# breakout.net
KiCad netlist of a schematic drawn in EAGLE
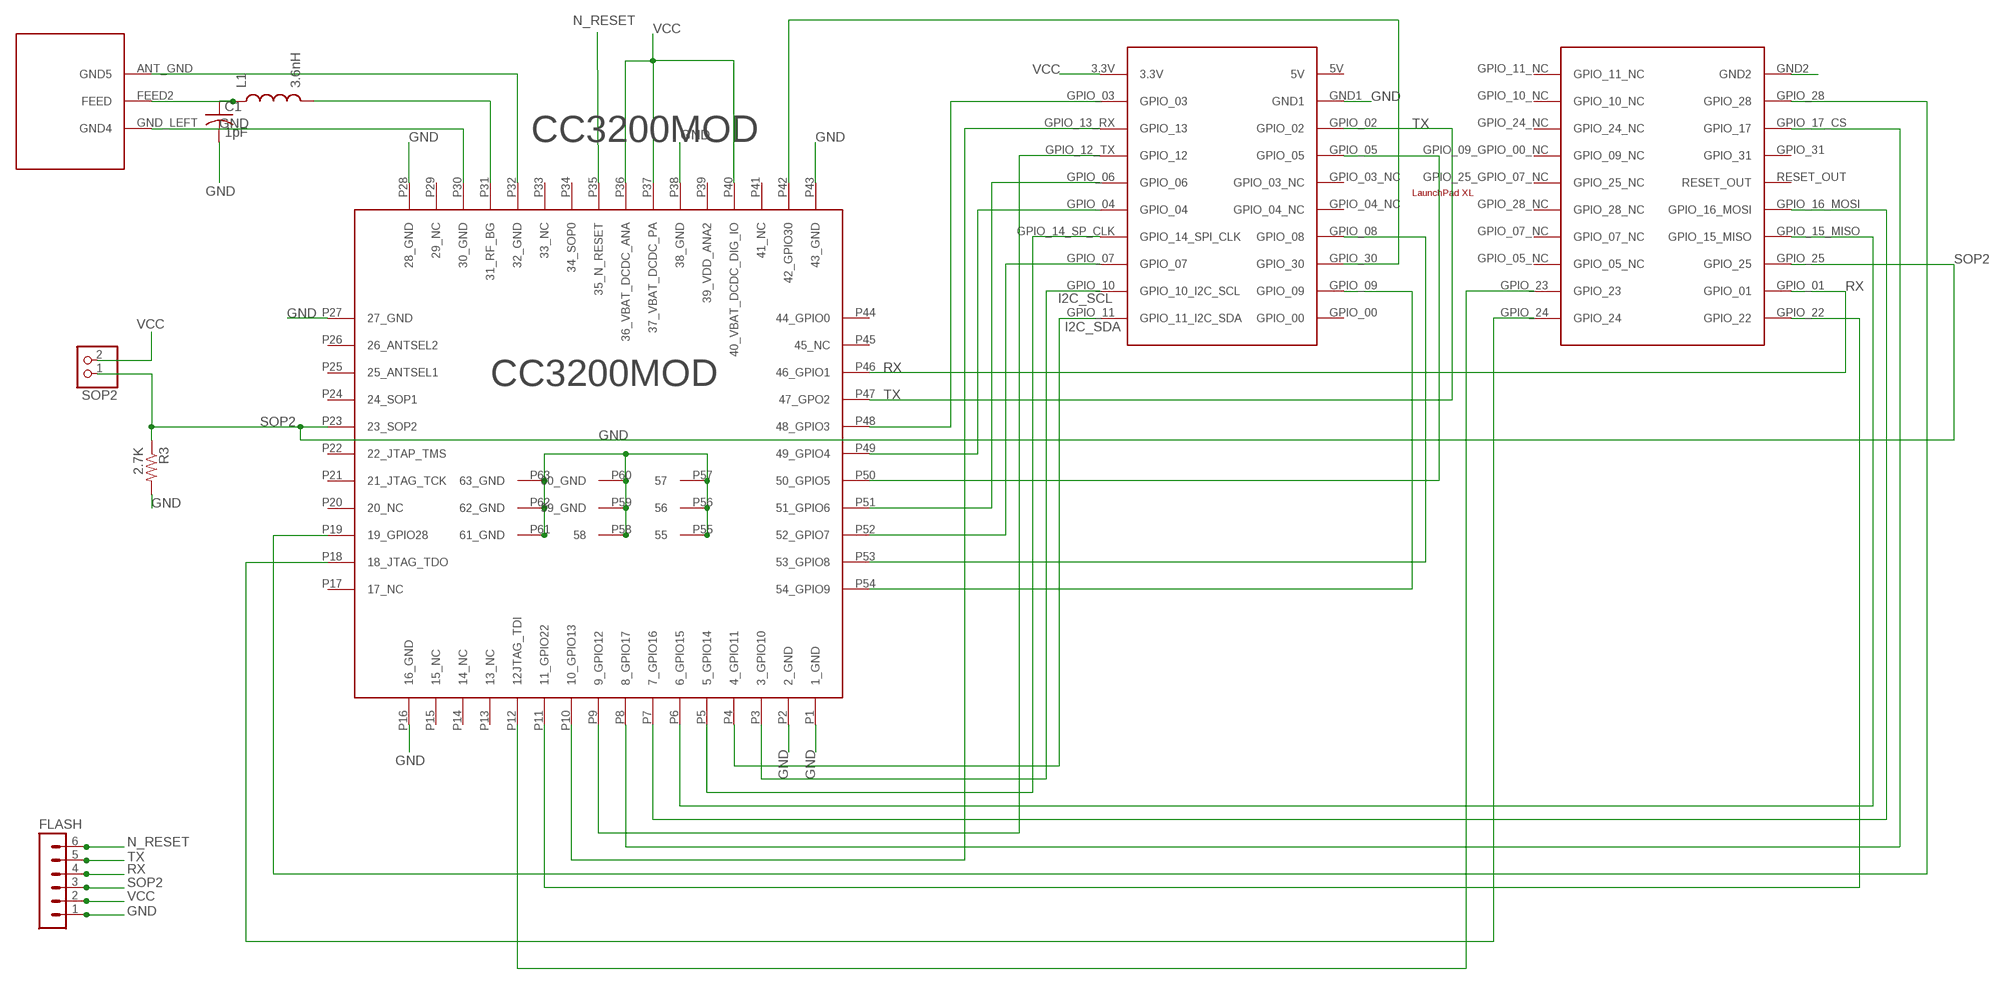
[diagram p0: schematic, sheet 1]
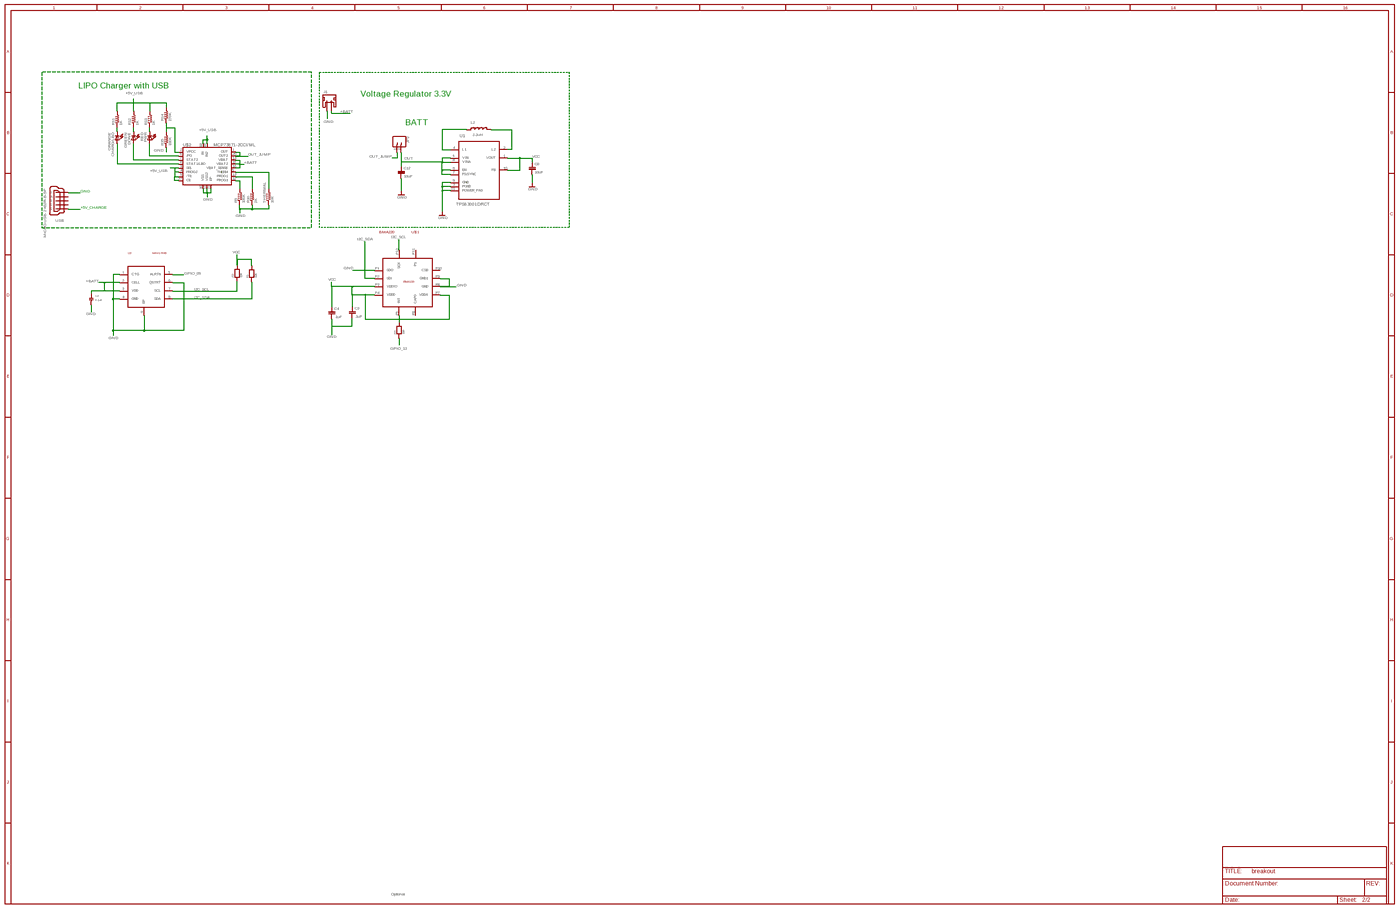
[diagram p1: schematic, sheet 2, overview]
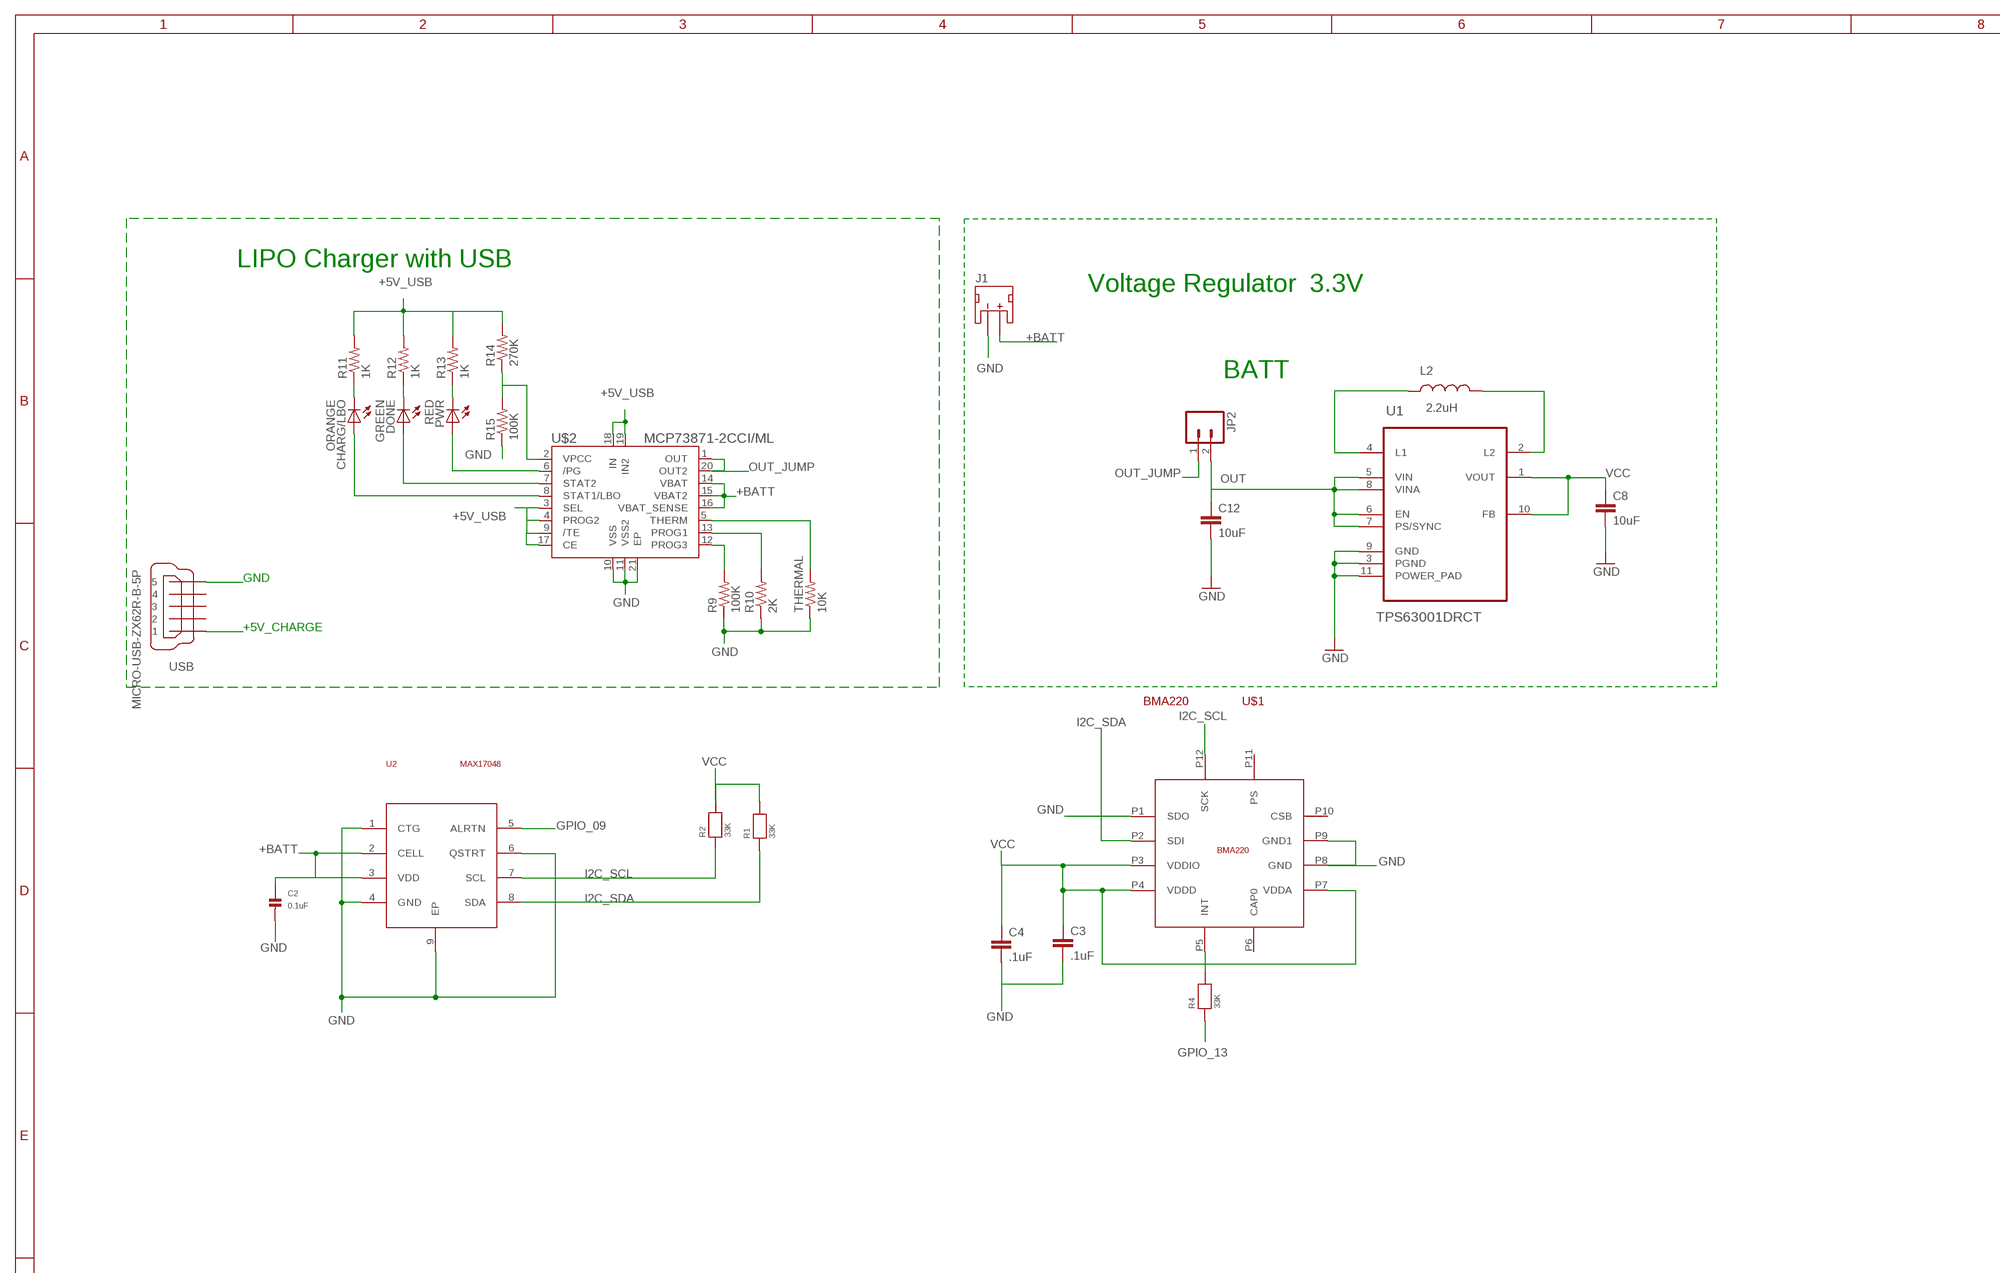
[diagram p2: schematic, sheet 2, part 1 of 4]
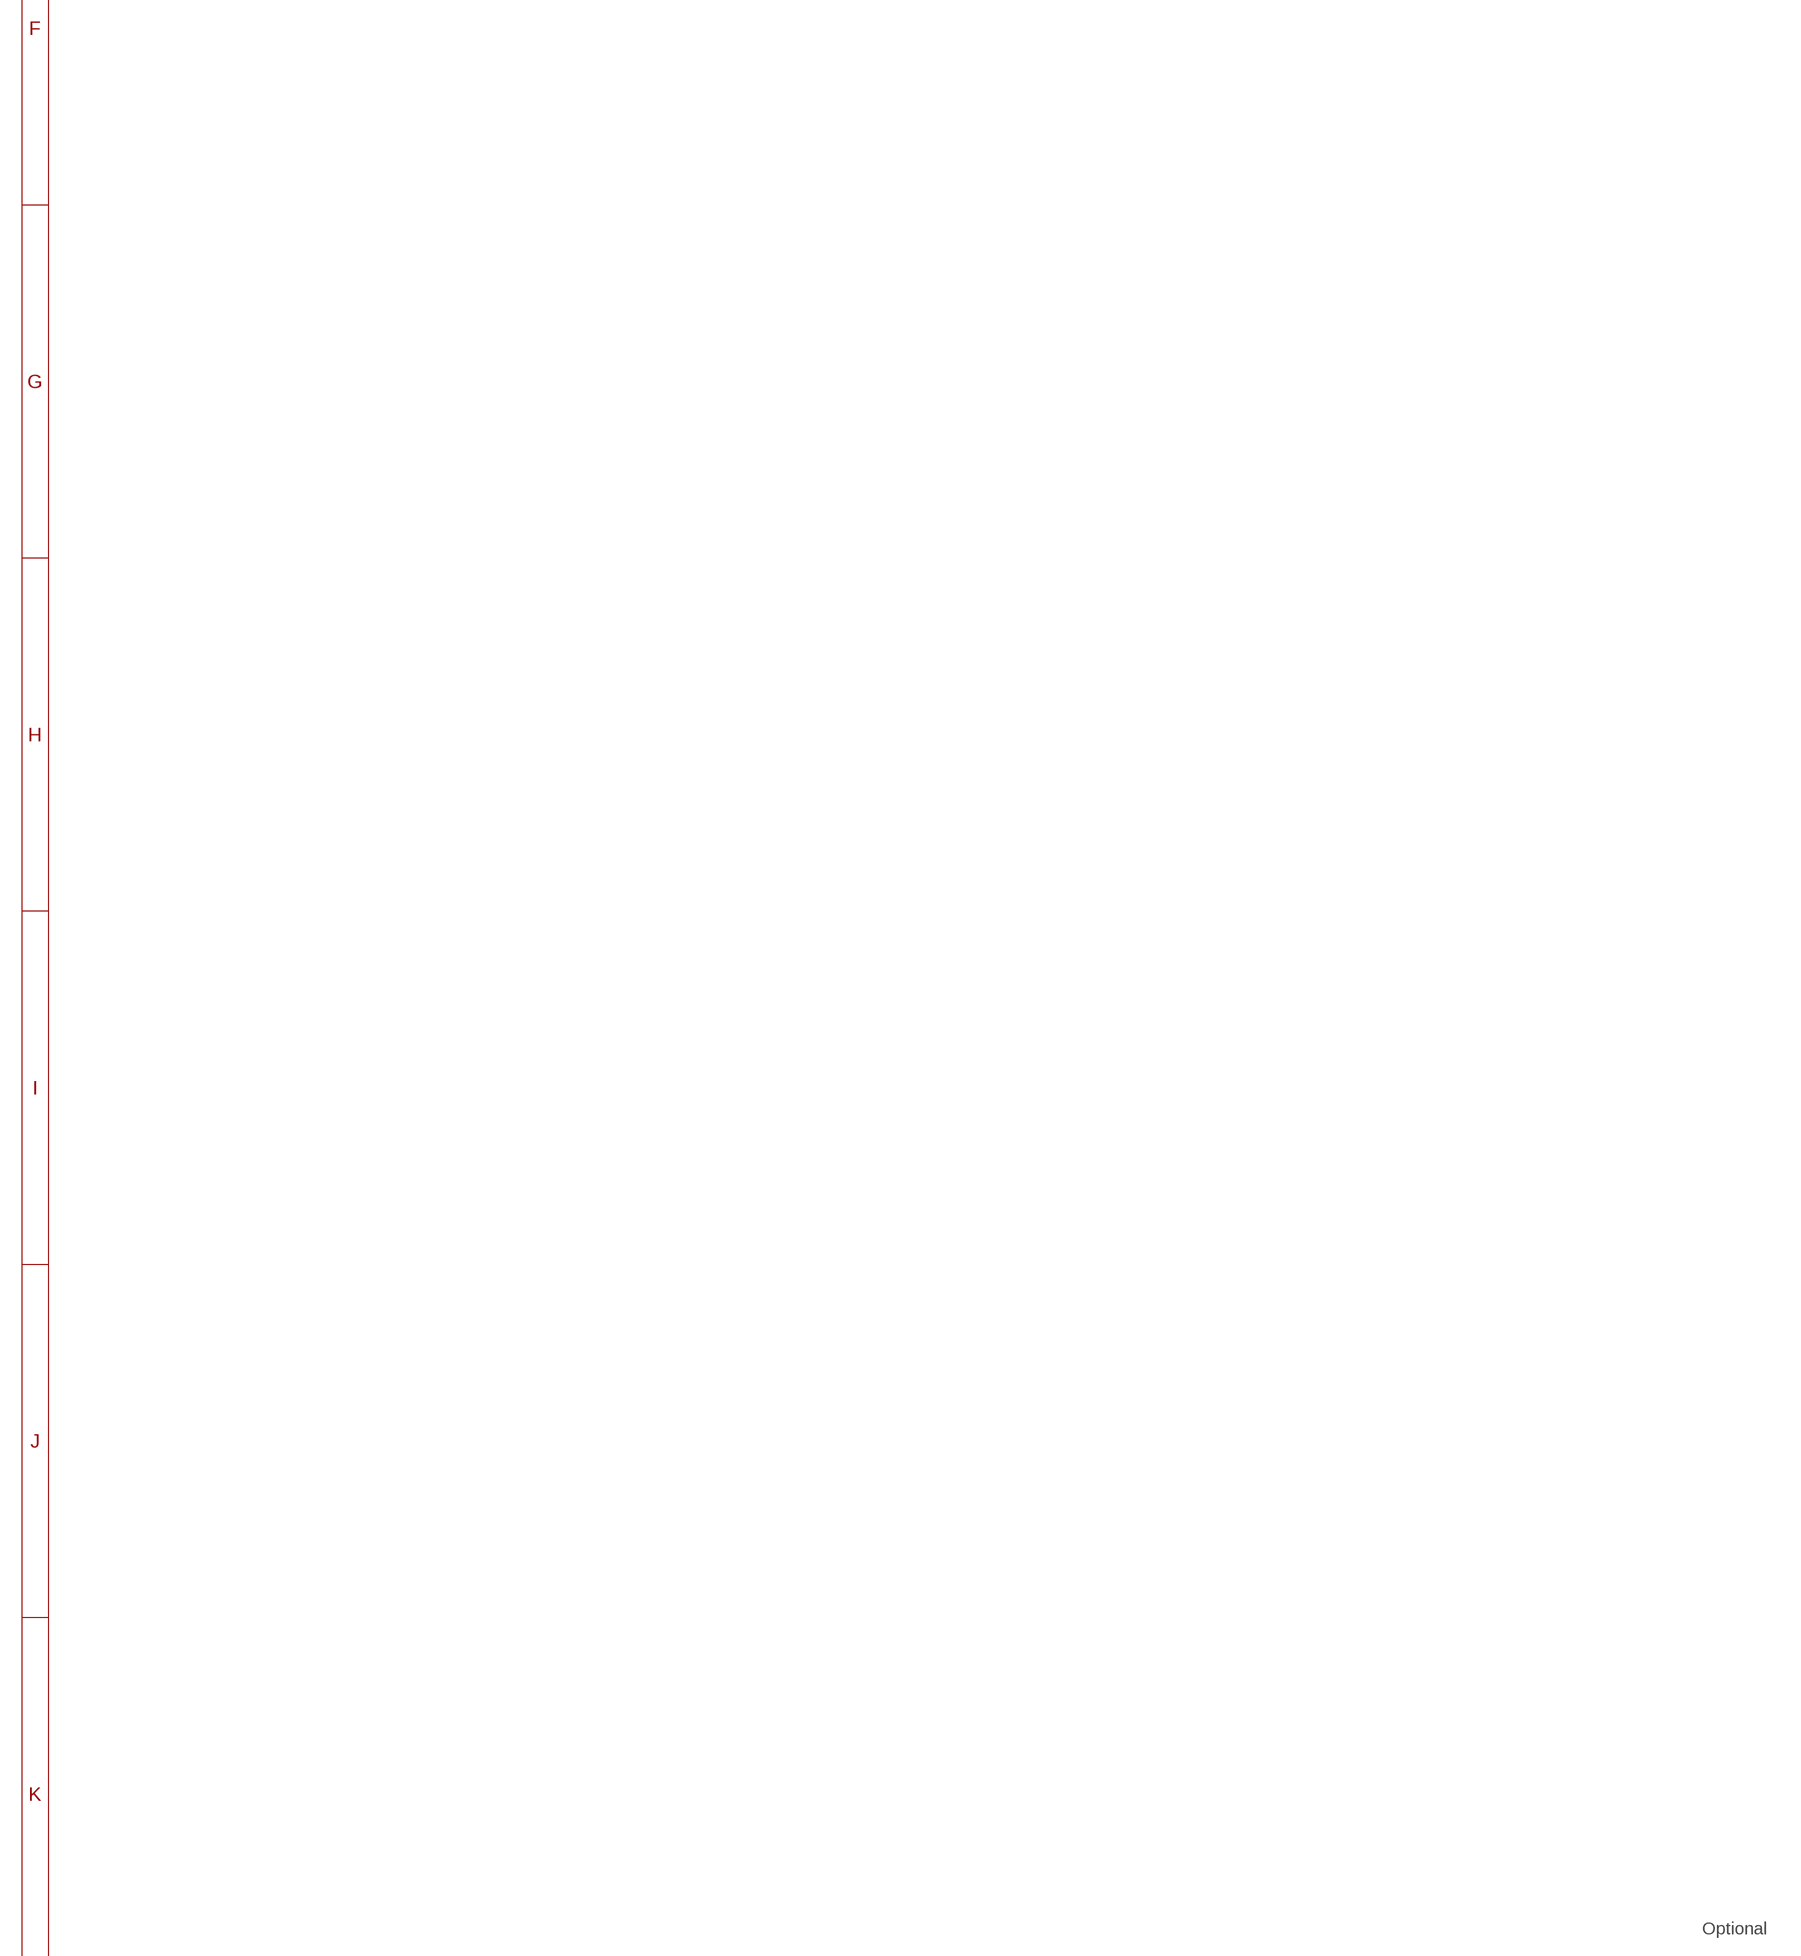
[diagram p3: schematic, sheet 2, part 2 of 4]
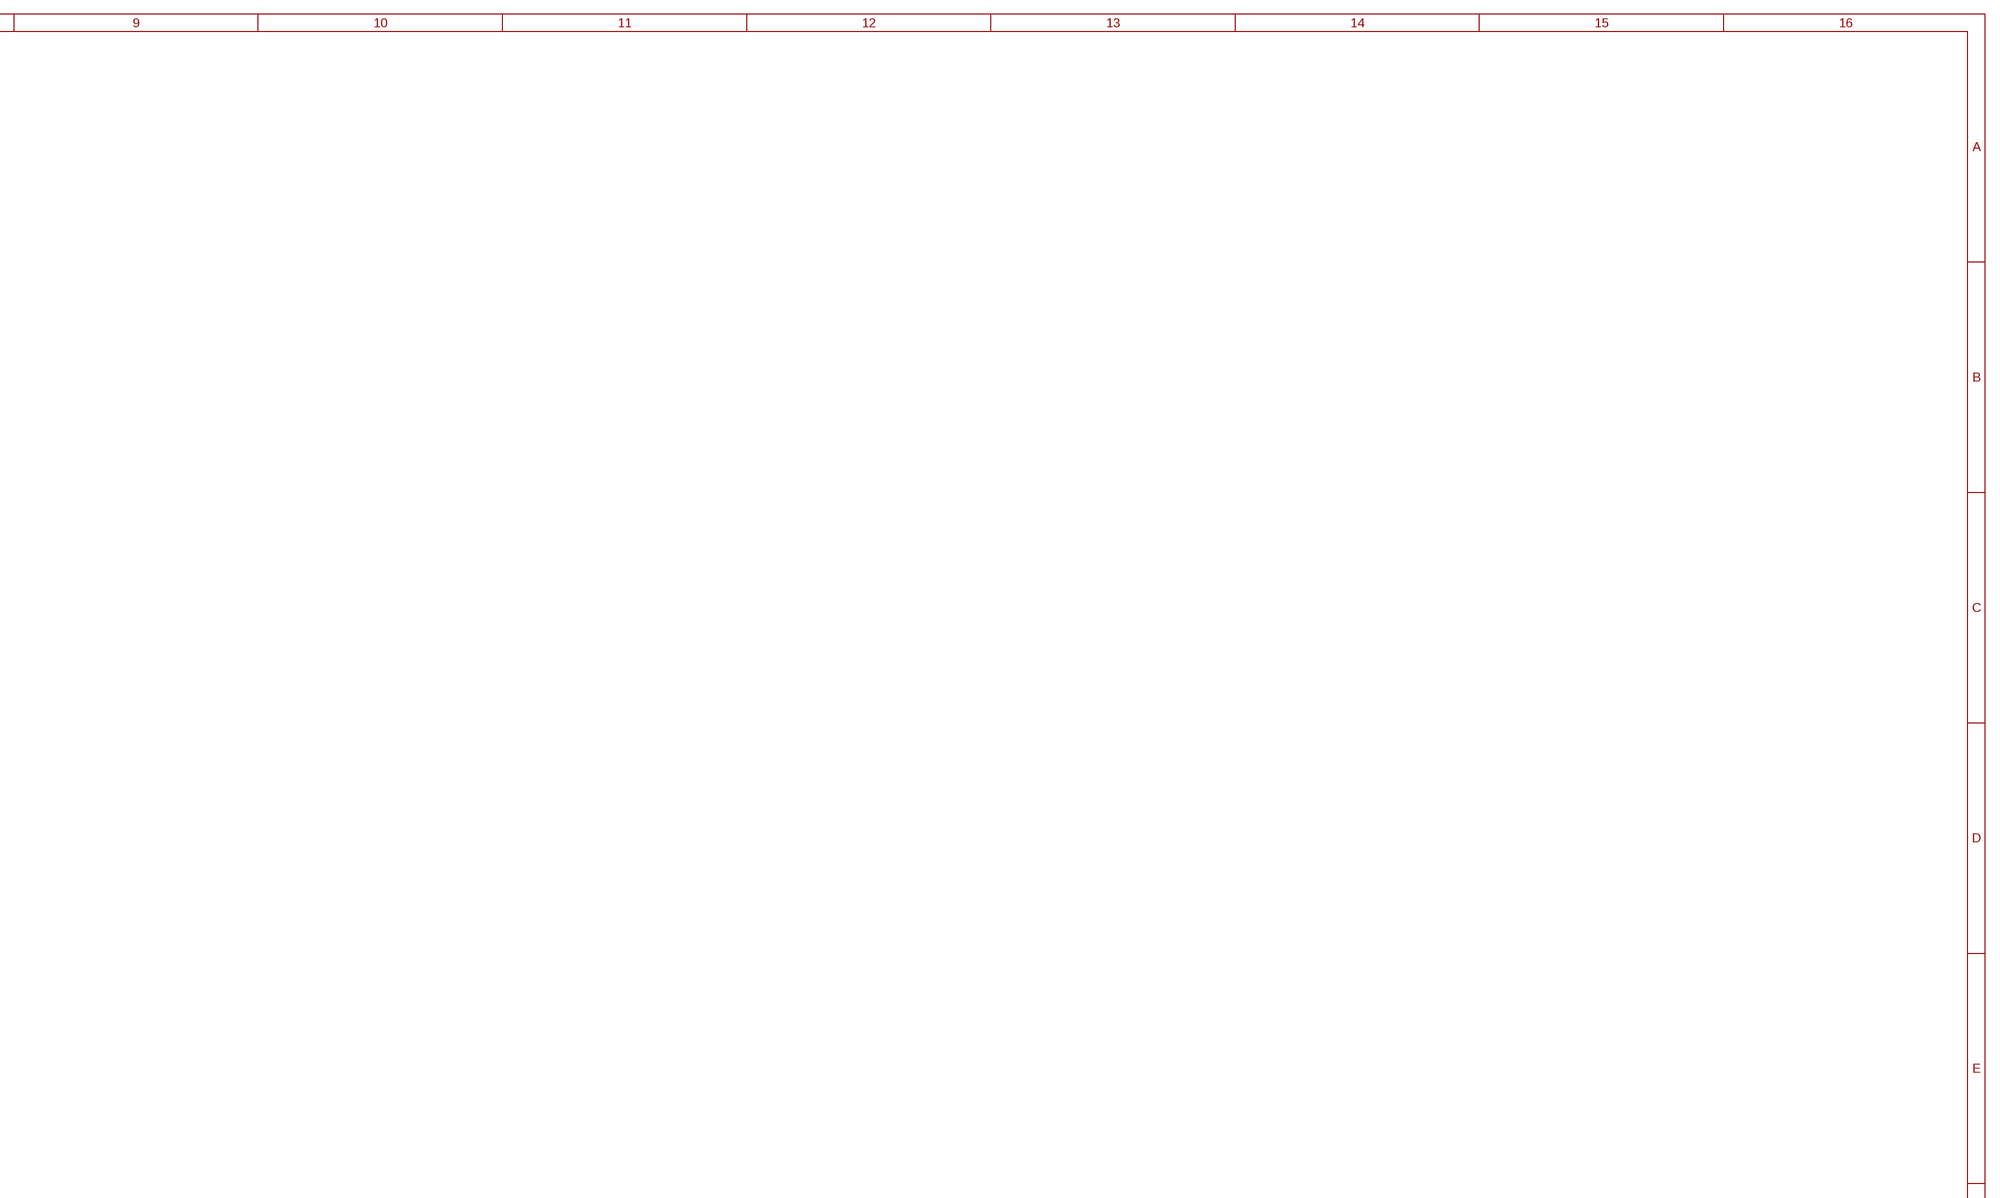
[diagram p4: schematic, sheet 2, part 3 of 4]
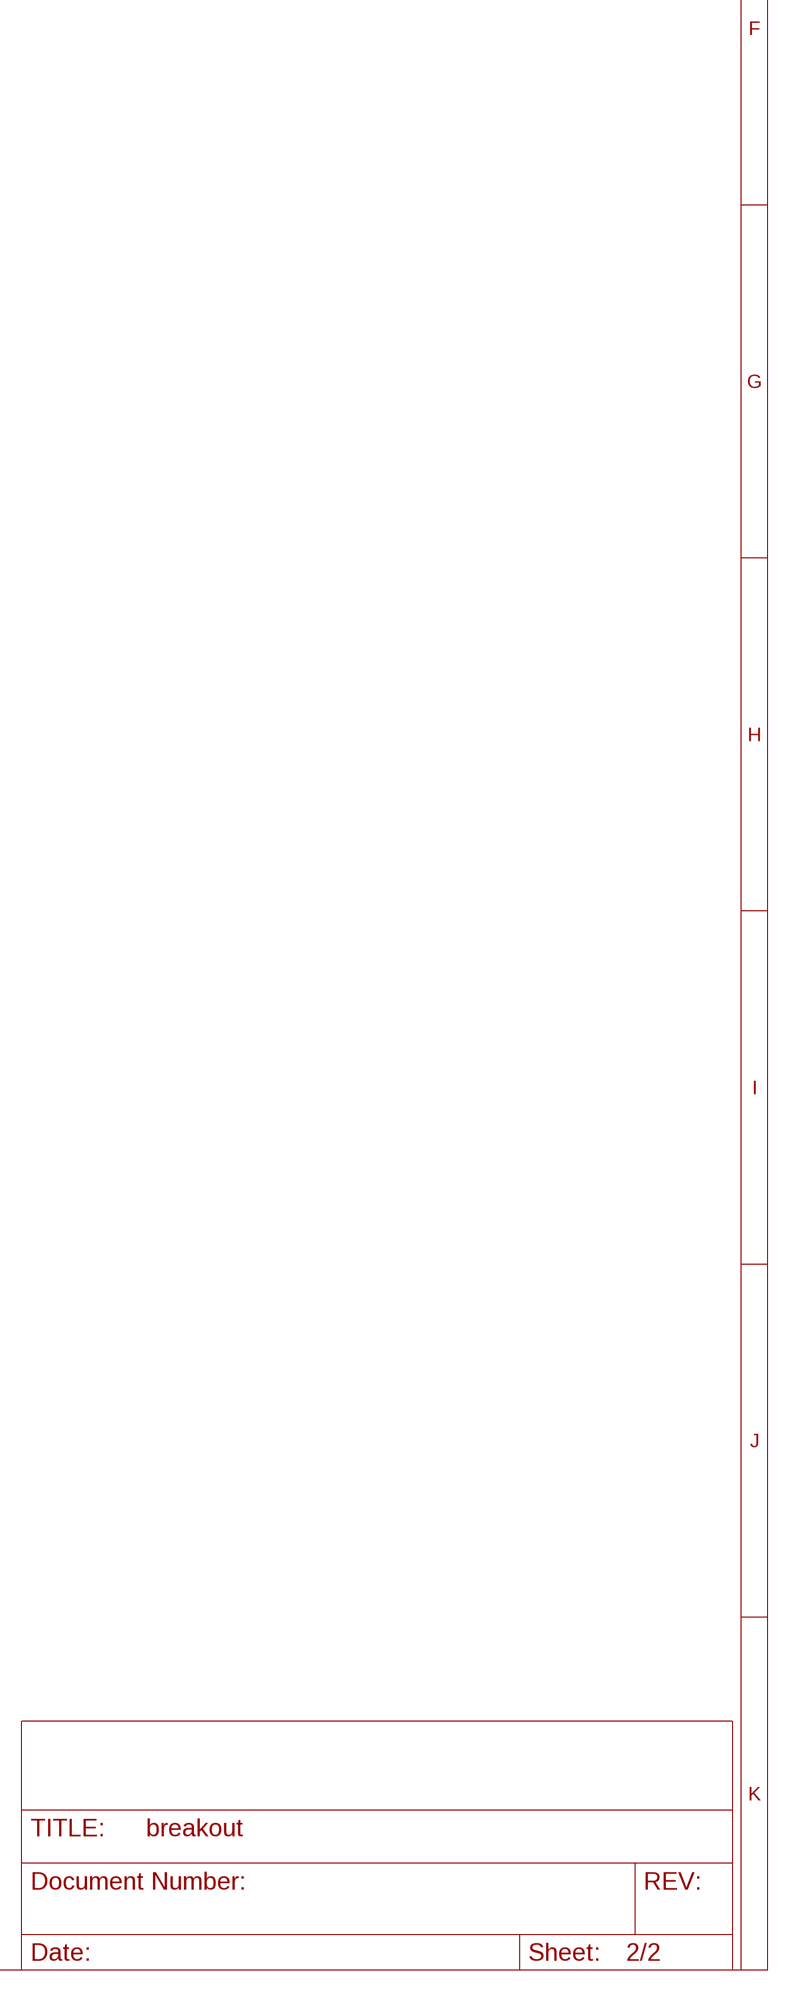
[diagram p5: schematic, sheet 2, part 4 of 4]

(export (version "E")
  (design (tool "Eeschema 10.0.6"))
  (components
    (comp (ref "ANT_PAD")
      (value "ANT")
      (footprint "eagle-import:ANT")
      (libsource (lib "eagle-import") (part "ANT"))
    )
    (comp (ref "C1")
      (value "1pF")
      (footprint "eagle-import:C0402")
      (libsource (lib "eagle-import") (part "C-USC0402"))
    )
    (comp (ref "CC3200MOD")
      (value "CC3200")
      (footprint "eagle-import:CC3200MOD")
      (libsource (lib "eagle-import") (part "CC3200"))
    )
    (comp (ref "FLASH")
      (value "MA06-1")
      (footprint "eagle-import:MA06-1")
      (libsource (lib "eagle-import") (part "MA06-1"))
    )
    (comp (ref "L1")
      (value "3.6nH")
      (footprint "eagle-import:C0402")
      (libsource (lib "eagle-import") (part "INDUCTOR-SPARKFUN0402"))
    )
    (comp (ref "R3")
      (value "2.7K")
      (footprint "eagle-import:0603-RES")
      (libsource (lib "eagle-import") (part "RESISTOR0603"))
    )
    (comp (ref "SOP2")
      (value "PINHD-1X2")
      (footprint "eagle-import:1X02")
      (libsource (lib "eagle-import") (part "PINHD-1X2"))
    )
    (comp (ref "U11")
      (value "XL")
      (footprint "eagle-import:LAUNCHPADXL")
      (libsource (lib "eagle-import") (part "XL"))
    )
    (comp (ref "C2")
      (value "0.1uF")
      (footprint "eagle-import:0402")
      (libsource (lib "eagle-import") (part "CAP_CERAMIC0402"))
    )
    (comp (ref "C3")
      (value ".1uF")
      (footprint "eagle-import:C0603")
      (libsource (lib "eagle-import") (part "C-EUC0603"))
    )
    (comp (ref "C4")
      (value ".1uF")
      (footprint "eagle-import:C0603")
      (libsource (lib "eagle-import") (part "C-EUC0603"))
    )
    (comp (ref "C8")
      (value "10uF")
      (footprint "eagle-import:C0603")
      (libsource (lib "eagle-import") (part "C-EUC0603"))
    )
    (comp (ref "C12")
      (value "10uF")
      (footprint "eagle-import:C0603")
      (libsource (lib "eagle-import") (part "C-EUC0603"))
    )
    (comp (ref "CHARG/LBO")
      (value "ORANGE")
      (footprint "eagle-import:SML0603")
      (libsource (lib "eagle-import") (part "LEDSML0603"))
    )
    (comp (ref "DONE")
      (value "GREEN")
      (footprint "eagle-import:SML0603")
      (libsource (lib "eagle-import") (part "LEDSML0603"))
    )
    (comp (ref "J1")
      (value "JST_2MM_MALE")
      (footprint "eagle-import:JST-2-SMD")
      (libsource (lib "eagle-import") (part "JST_2MM_MALE"))
    )
    (comp (ref "JP2")
      (value "M02PTH")
      (footprint "eagle-import:1X02")
      (libsource (lib "eagle-import") (part "M02PTH"))
    )
    (comp (ref "L2")
      (value "2.2uH")
      (footprint "eagle-import:0805")
      (libsource (lib "eagle-import") (part "INDUCTOR0805"))
    )
    (comp (ref "PWR")
      (value "RED")
      (footprint "eagle-import:SML0603")
      (libsource (lib "eagle-import") (part "LEDSML0603"))
    )
    (comp (ref "R1")
      (value "33K")
      (footprint "eagle-import:0402")
      (libsource (lib "eagle-import") (part "RESISTOR0402"))
    )
    (comp (ref "R2")
      (value "33K")
      (footprint "eagle-import:0402")
      (libsource (lib "eagle-import") (part "RESISTOR0402"))
    )
    (comp (ref "R4")
      (value "33K")
      (footprint "eagle-import:0402")
      (libsource (lib "eagle-import") (part "RESISTOR0402"))
    )
    (comp (ref "R9")
      (value "100K")
      (footprint "eagle-import:0603-RES")
      (libsource (lib "eagle-import") (part "RESISTOR0603-RES"))
    )
    (comp (ref "R10")
      (value "2K")
      (footprint "eagle-import:0603-RES")
      (libsource (lib "eagle-import") (part "RESISTOR0603-RES"))
    )
    (comp (ref "R11")
      (value "1K")
      (footprint "eagle-import:0603-RES")
      (libsource (lib "eagle-import") (part "RESISTOR0603-RES"))
    )
    (comp (ref "R12")
      (value "1K")
      (footprint "eagle-import:0603-RES")
      (libsource (lib "eagle-import") (part "RESISTOR0603-RES"))
    )
    (comp (ref "R13")
      (value "1K")
      (footprint "eagle-import:0603-RES")
      (libsource (lib "eagle-import") (part "RESISTOR0603-RES"))
    )
    (comp (ref "R14")
      (value "270K")
      (footprint "eagle-import:0603-RES")
      (libsource (lib "eagle-import") (part "RESISTOR0603-RES"))
    )
    (comp (ref "R15")
      (value "100K")
      (footprint "eagle-import:0603-RES")
      (libsource (lib "eagle-import") (part "RESISTOR0603-RES"))
    )
    (comp (ref "THERMAL")
      (value "10K")
      (footprint "eagle-import:0603-RES")
      (libsource (lib "eagle-import") (part "RESISTOR0603-RES"))
    )
    (comp (ref "U$1")
      (value "BMA220")
      (footprint "eagle-import:BMA222")
      (libsource (lib "eagle-import") (part "BMA220"))
    )
    (comp (ref "U$2")
      (value "MCP73871-2CCI/ML")
      (footprint "eagle-import:QFN20-4X4")
      (libsource (lib "eagle-import") (part "MCP73871ML-2CCI/"))
    )
    (comp (ref "U1")
      (value "TPS63001DRCT")
      (footprint "eagle-import:SON50P300X300X100-11N")
      (libsource (lib "eagle-import") (part "TPS63001DRCT"))
    )
    (comp (ref "U2")
      (value "MAX17048")
      (footprint "eagle-import:DFN200X200X80-9N")
      (libsource (lib "eagle-import") (part "MAX17048"))
    )
    (comp (ref "USB")
      (value "MICRO-USB-ZX62R-B-5P")
      (footprint "eagle-import:ZX62R-B-5P")
      (libsource (lib "eagle-import") (part "MICRO-USB-ZX62R-B-5P"))
    )
  )
  (nets
    (net (code "1") (name "+5V_USB") (class "Default")
      (node (ref "R11") (pin "2") (pinfunction "2_2") (pintype "passive"))
      (node (ref "R12") (pin "2") (pinfunction "2_2") (pintype "passive"))
      (node (ref "R13") (pin "2") (pinfunction "2_2") (pintype "passive"))
      (node (ref "R14") (pin "2") (pinfunction "2_2") (pintype "passive"))
      (node (ref "U$2") (pin "17") (pinfunction "CE_17") (pintype "input"))
      (node (ref "U$2") (pin "18") (pinfunction "IN_18") (pintype "power_in"))
      (node (ref "U$2") (pin "19") (pinfunction "IN2_19") (pintype "power_in"))
      (node (ref "U$2") (pin "3") (pinfunction "SEL_3") (pintype "input"))
      (node (ref "U$2") (pin "4") (pinfunction "PROG2_4") (pintype "input"))
      (node (ref "U$2") (pin "9") (pinfunction "/TE_9") (pintype "input"))
      (node (ref "USB") (pin "1") (pinfunction "1_1") (pintype "input"))
    )
    (net (code "2") (name "+BATT") (class "Default")
      (node (ref "C2") (pin "1") (pinfunction "P$1_1") (pintype "passive"))
      (node (ref "J1") (pin "2") (pinfunction "+_2") (pintype "bidirectional"))
      (node (ref "U$2") (pin "14") (pinfunction "VBAT_14") (pintype "bidirectional"))
      (node (ref "U$2") (pin "15") (pinfunction "VBAT2_15") (pintype "bidirectional"))
      (node (ref "U$2") (pin "16") (pinfunction "VBAT_SENSE_16") (pintype "bidirectional"))
      (node (ref "U2") (pin "2") (pinfunction "CELL_2") (pintype "bidirectional"))
      (node (ref "U2") (pin "3") (pinfunction "VDD_3") (pintype "bidirectional"))
    )
    (net (code "3") (name "GND") (class "Default")
      (node (ref "ANT_PAD") (pin "ANT_GND") (pinfunction "GND5_ANT_GND") (pintype "bidirectional"))
      (node (ref "ANT_PAD") (pin "GND_LEFT") (pinfunction "GND4_GND_LEFT") (pintype "bidirectional"))
      (node (ref "C1") (pin "2") (pinfunction "2_2") (pintype "passive"))
      (node (ref "C12") (pin "2") (pinfunction "2_2") (pintype "passive"))
      (node (ref "C2") (pin "2") (pinfunction "P$2_2") (pintype "passive"))
      (node (ref "C3") (pin "2") (pinfunction "2_2") (pintype "passive"))
      (node (ref "C4") (pin "2") (pinfunction "2_2") (pintype "passive"))
      (node (ref "C8") (pin "2") (pinfunction "2_2") (pintype "passive"))
      (node (ref "CC3200MOD") (pin "P1") (pinfunction "1_GND_P1") (pintype "bidirectional"))
      (node (ref "CC3200MOD") (pin "P16") (pinfunction "16_GND_P16") (pintype "bidirectional"))
      (node (ref "CC3200MOD") (pin "P2") (pinfunction "2_GND_P2") (pintype "bidirectional"))
      (node (ref "CC3200MOD") (pin "P27") (pinfunction "27_GND_P27") (pintype "bidirectional"))
      (node (ref "CC3200MOD") (pin "P28") (pinfunction "28_GND_P28") (pintype "bidirectional"))
      (node (ref "CC3200MOD") (pin "P30") (pinfunction "30_GND_P30") (pintype "bidirectional"))
      (node (ref "CC3200MOD") (pin "P32") (pinfunction "32_GND_P32") (pintype "bidirectional"))
      (node (ref "CC3200MOD") (pin "P38") (pinfunction "38_GND_P38") (pintype "bidirectional"))
      (node (ref "CC3200MOD") (pin "P43") (pinfunction "43_GND_P43") (pintype "bidirectional"))
      (node (ref "CC3200MOD") (pin "P55") (pinfunction "55_P55") (pintype "bidirectional"))
      (node (ref "CC3200MOD") (pin "P56") (pinfunction "56_P56") (pintype "bidirectional"))
      (node (ref "CC3200MOD") (pin "P57") (pinfunction "57_P57") (pintype "bidirectional"))
      (node (ref "CC3200MOD") (pin "P58") (pinfunction "58_P58") (pintype "bidirectional"))
      (node (ref "CC3200MOD") (pin "P59") (pinfunction "59_GND_P59") (pintype "bidirectional"))
      (node (ref "CC3200MOD") (pin "P60") (pinfunction "60_GND_P60") (pintype "bidirectional"))
      (node (ref "CC3200MOD") (pin "P61") (pinfunction "61_GND_P61") (pintype "bidirectional"))
      (node (ref "CC3200MOD") (pin "P62") (pinfunction "62_GND_P62") (pintype "bidirectional"))
      (node (ref "CC3200MOD") (pin "P63") (pinfunction "63_GND_P63") (pintype "bidirectional"))
      (node (ref "FLASH") (pin "1") (pinfunction "1_1") (pintype "passive"))
      (node (ref "J1") (pin "1") (pinfunction "-_1") (pintype "bidirectional"))
      (node (ref "R10") (pin "1") (pinfunction "1_1") (pintype "passive"))
      (node (ref "R15") (pin "1") (pinfunction "1_1") (pintype "passive"))
      (node (ref "R3") (pin "2") (pinfunction "2_2") (pintype "passive"))
      (node (ref "R9") (pin "1") (pinfunction "1_1") (pintype "passive"))
      (node (ref "THERMAL") (pin "1") (pinfunction "1_1") (pintype "passive"))
      (node (ref "U$1") (pin "P1") (pinfunction "SDO_P1") (pintype "bidirectional"))
      (node (ref "U$1") (pin "P8") (pinfunction "GND_P8") (pintype "bidirectional"))
      (node (ref "U$1") (pin "P9") (pinfunction "GND1_P9") (pintype "bidirectional"))
      (node (ref "U$2") (pin "10") (pinfunction "VSS_10") (pintype "power_in"))
      (node (ref "U$2") (pin "11") (pinfunction "VSS2_11") (pintype "power_in"))
      (node (ref "U$2") (pin "21") (pinfunction "EP_21") (pintype "power_in"))
      (node (ref "U1") (pin "11") (pinfunction "POWER_PAD_11") (pintype "passive"))
      (node (ref "U1") (pin "3") (pinfunction "PGND_3") (pintype "passive"))
      (node (ref "U1") (pin "9") (pinfunction "GND_9") (pintype "passive"))
      (node (ref "U11") (pin "GND1") (pinfunction "GND1_GND1") (pintype "bidirectional"))
      (node (ref "U11") (pin "GND2") (pinfunction "GND2_GND2") (pintype "bidirectional"))
      (node (ref "U2") (pin "1") (pinfunction "CTG_1") (pintype "bidirectional"))
      (node (ref "U2") (pin "4") (pinfunction "GND_4") (pintype "bidirectional"))
      (node (ref "U2") (pin "6") (pinfunction "QSTRT_6") (pintype "bidirectional"))
      (node (ref "U2") (pin "9") (pinfunction "EP_9") (pintype "bidirectional"))
      (node (ref "USB") (pin "5") (pinfunction "5_5") (pintype "input"))
    )
    (net (code "4") (name "GPIO_09") (class "Default")
      (node (ref "CC3200MOD") (pin "P54") (pinfunction "54_GPIO9_P54") (pintype "bidirectional"))
      (node (ref "U11") (pin "GPIO_09") (pinfunction "GPIO_09_GPIO_09") (pintype "bidirectional"))
      (node (ref "U2") (pin "5") (pinfunction "ALRTN_5") (pintype "bidirectional"))
    )
    (net (code "5") (name "GPIO_13") (class "Default")
      (node (ref "R4") (pin "1") (pinfunction "1_1") (pintype "passive"))
    )
    (net (code "6") (name "I2C_SCL") (class "Default")
      (node (ref "CC3200MOD") (pin "P3") (pinfunction "3_GPIO10_P3") (pintype "bidirectional"))
      (node (ref "R2") (pin "1") (pinfunction "1_1") (pintype "passive"))
      (node (ref "U$1") (pin "P12") (pinfunction "SCK_P12") (pintype "bidirectional"))
      (node (ref "U11") (pin "GPIO_10") (pinfunction "GPIO_10_I2C_SCL_GPIO_10") (pintype "bidirectional"))
      (node (ref "U2") (pin "7") (pinfunction "SCL_7") (pintype "bidirectional"))
    )
    (net (code "7") (name "I2C_SDA") (class "Default")
      (node (ref "CC3200MOD") (pin "P4") (pinfunction "4_GPIO11_P4") (pintype "bidirectional"))
      (node (ref "R1") (pin "1") (pinfunction "1_1") (pintype "passive"))
      (node (ref "U$1") (pin "P2") (pinfunction "SDI_P2") (pintype "bidirectional"))
      (node (ref "U11") (pin "GPIO_11") (pinfunction "GPIO_11_I2C_SDA_GPIO_11") (pintype "bidirectional"))
      (node (ref "U2") (pin "8") (pinfunction "SDA_8") (pintype "bidirectional"))
    )
    (net (code "8") (name "N_RESET") (class "Default")
      (node (ref "CC3200MOD") (pin "P35") (pinfunction "35_N_RESET_P35") (pintype "bidirectional"))
      (node (ref "FLASH") (pin "6") (pinfunction "6_6") (pintype "passive"))
    )
    (net (code "9") (name "Net-(ANT_PAD-FEED)") (class "Default")
      (node (ref "ANT_PAD") (pin "FEED2") (pinfunction "FEED_FEED2") (pintype "bidirectional"))
      (node (ref "C1") (pin "1") (pinfunction "1_1") (pintype "passive"))
      (node (ref "L1") (pin "1") (pinfunction "1_1") (pintype "passive"))
    )
    (net (code "10") (name "Net-(CC3200MOD-5_GPIO14)") (class "Default")
      (node (ref "CC3200MOD") (pin "P5") (pinfunction "5_GPIO14_P5") (pintype "bidirectional"))
      (node (ref "U11") (pin "GPIO_14_SP_CLK") (pinfunction "GPIO_14_SPI_CLK_GPIO_14_SP_CLK") (pintype "bidirectional"))
    )
    (net (code "11") (name "Net-(CC3200MOD-6_GPIO15)") (class "Default")
      (node (ref "CC3200MOD") (pin "P6") (pinfunction "6_GPIO15_P6") (pintype "bidirectional"))
      (node (ref "U11") (pin "GPIO_15_MISO") (pinfunction "GPIO_15_MISO_GPIO_15_MISO") (pintype "bidirectional"))
    )
    (net (code "12") (name "Net-(CC3200MOD-7_GPIO16)") (class "Default")
      (node (ref "CC3200MOD") (pin "P7") (pinfunction "7_GPIO16_P7") (pintype "bidirectional"))
      (node (ref "U11") (pin "GPIO_16_MOSI") (pinfunction "GPIO_16_MOSI_GPIO_16_MOSI") (pintype "bidirectional"))
    )
    (net (code "13") (name "Net-(CC3200MOD-8_GPIO17)") (class "Default")
      (node (ref "CC3200MOD") (pin "P8") (pinfunction "8_GPIO17_P8") (pintype "bidirectional"))
      (node (ref "U11") (pin "GPIO_17_CS") (pinfunction "GPIO_17_GPIO_17_CS") (pintype "bidirectional"))
    )
    (net (code "14") (name "Net-(CC3200MOD-9_GPIO12)") (class "Default")
      (node (ref "CC3200MOD") (pin "P9") (pinfunction "9_GPIO12_P9") (pintype "bidirectional"))
      (node (ref "U11") (pin "GPIO_12_TX") (pinfunction "GPIO_12_GPIO_12_TX") (pintype "bidirectional"))
    )
    (net (code "15") (name "Net-(CC3200MOD-10_GPIO13)") (class "Default")
      (node (ref "CC3200MOD") (pin "P10") (pinfunction "10_GPIO13_P10") (pintype "bidirectional"))
      (node (ref "U11") (pin "GPIO_13_RX") (pinfunction "GPIO_13_GPIO_13_RX") (pintype "bidirectional"))
    )
    (net (code "16") (name "Net-(CC3200MOD-11_GPIO22)") (class "Default")
      (node (ref "CC3200MOD") (pin "P11") (pinfunction "11_GPIO22_P11") (pintype "bidirectional"))
      (node (ref "U11") (pin "GPIO_22") (pinfunction "GPIO_22_GPIO_22") (pintype "bidirectional"))
    )
    (net (code "17") (name "Net-(CC3200MOD-12JTAG_TDI)") (class "Default")
      (node (ref "CC3200MOD") (pin "P12") (pinfunction "12JTAG_TDI_P12") (pintype "bidirectional"))
      (node (ref "U11") (pin "GPIO_23") (pinfunction "GPIO_23_GPIO_23") (pintype "bidirectional"))
    )
    (net (code "18") (name "Net-(CC3200MOD-18_JTAG_TDO)") (class "Default")
      (node (ref "CC3200MOD") (pin "P18") (pinfunction "18_JTAG_TDO_P18") (pintype "bidirectional"))
      (node (ref "U11") (pin "GPIO_24") (pinfunction "GPIO_24_GPIO_24") (pintype "bidirectional"))
    )
    (net (code "19") (name "Net-(CC3200MOD-19_GPIO28)") (class "Default")
      (node (ref "CC3200MOD") (pin "P19") (pinfunction "19_GPIO28_P19") (pintype "bidirectional"))
      (node (ref "U11") (pin "GPIO_28") (pinfunction "GPIO_28_GPIO_28") (pintype "bidirectional"))
    )
    (net (code "20") (name "Net-(CC3200MOD-31_RF_BG)") (class "Default")
      (node (ref "CC3200MOD") (pin "P31") (pinfunction "31_RF_BG_P31") (pintype "bidirectional"))
      (node (ref "L1") (pin "2") (pinfunction "2_2") (pintype "passive"))
    )
    (net (code "21") (name "Net-(CC3200MOD-42_GPIO30)") (class "Default")
      (node (ref "CC3200MOD") (pin "P42") (pinfunction "42_GPIO30_P42") (pintype "bidirectional"))
      (node (ref "U11") (pin "GPIO_30") (pinfunction "GPIO_30_GPIO_30") (pintype "bidirectional"))
    )
    (net (code "22") (name "Net-(CC3200MOD-48_GPIO3)") (class "Default")
      (node (ref "CC3200MOD") (pin "P48") (pinfunction "48_GPIO3_P48") (pintype "bidirectional"))
      (node (ref "U11") (pin "GPIO_03") (pinfunction "GPIO_03_GPIO_03") (pintype "bidirectional"))
    )
    (net (code "23") (name "Net-(CC3200MOD-49_GPIO4)") (class "Default")
      (node (ref "CC3200MOD") (pin "P49") (pinfunction "49_GPIO4_P49") (pintype "bidirectional"))
      (node (ref "U11") (pin "GPIO_04") (pinfunction "GPIO_04_GPIO_04") (pintype "bidirectional"))
    )
    (net (code "24") (name "Net-(CC3200MOD-50_GPIO5)") (class "Default")
      (node (ref "CC3200MOD") (pin "P50") (pinfunction "50_GPIO5_P50") (pintype "bidirectional"))
      (node (ref "U11") (pin "GPIO_05") (pinfunction "GPIO_05_GPIO_05") (pintype "bidirectional"))
    )
    (net (code "25") (name "Net-(CC3200MOD-51_GPIO6)") (class "Default")
      (node (ref "CC3200MOD") (pin "P51") (pinfunction "51_GPIO6_P51") (pintype "bidirectional"))
      (node (ref "U11") (pin "GPIO_06") (pinfunction "GPIO_06_GPIO_06") (pintype "bidirectional"))
    )
    (net (code "26") (name "Net-(CC3200MOD-52_GPIO7)") (class "Default")
      (node (ref "CC3200MOD") (pin "P52") (pinfunction "52_GPIO7_P52") (pintype "bidirectional"))
      (node (ref "U11") (pin "GPIO_07") (pinfunction "GPIO_07_GPIO_07") (pintype "bidirectional"))
    )
    (net (code "27") (name "Net-(CC3200MOD-53_GPIO8)") (class "Default")
      (node (ref "CC3200MOD") (pin "P53") (pinfunction "53_GPIO8_P53") (pintype "bidirectional"))
      (node (ref "U11") (pin "GPIO_08") (pinfunction "GPIO_08_GPIO_08") (pintype "bidirectional"))
    )
    (net (code "28") (name "Net-(CHARG/LBO-PadC)") (class "Default")
      (node (ref "CHARG/LBO") (pin "C") (pinfunction "C_C") (pintype "passive"))
      (node (ref "R11") (pin "1") (pinfunction "1_1") (pintype "passive"))
    )
    (net (code "29") (name "Net-(DONE-PadC)") (class "Default")
      (node (ref "DONE") (pin "C") (pinfunction "C_C") (pintype "passive"))
      (node (ref "R12") (pin "1") (pinfunction "1_1") (pintype "passive"))
    )
    (net (code "30") (name "Net-(PWR-PadC)") (class "Default")
      (node (ref "PWR") (pin "C") (pinfunction "C_C") (pintype "passive"))
      (node (ref "R13") (pin "1") (pinfunction "1_1") (pintype "passive"))
    )
    (net (code "31") (name "Net-(U$1-INT)") (class "Default")
      (node (ref "R4") (pin "2") (pinfunction "2_2") (pintype "passive"))
      (node (ref "U$1") (pin "P5") (pinfunction "INT_P5") (pintype "bidirectional"))
    )
    (net (code "32") (name "Net-(U$2-PROG1)") (class "Default")
      (node (ref "R10") (pin "2") (pinfunction "2_2") (pintype "passive"))
      (node (ref "U$2") (pin "13") (pinfunction "PROG1_13") (pintype "bidirectional"))
    )
    (net (code "33") (name "Net-(U$2-PROG3)") (class "Default")
      (node (ref "R9") (pin "2") (pinfunction "2_2") (pintype "passive"))
      (node (ref "U$2") (pin "12") (pinfunction "PROG3_12") (pintype "bidirectional"))
    )
    (net (code "34") (name "Net-(U$2-STAT1{slash}LBO)") (class "Default")
      (node (ref "CHARG/LBO") (pin "A") (pinfunction "A_A") (pintype "passive"))
      (node (ref "U$2") (pin "8") (pinfunction "STAT1/LBO_8") (pintype "open_collector"))
    )
    (net (code "35") (name "Net-(U$2-STAT2)") (class "Default")
      (node (ref "DONE") (pin "A") (pinfunction "A_A") (pintype "passive"))
      (node (ref "U$2") (pin "7") (pinfunction "STAT2_7") (pintype "open_collector"))
    )
    (net (code "36") (name "Net-(U$2-THERM)") (class "Default")
      (node (ref "THERMAL") (pin "2") (pinfunction "2_2") (pintype "passive"))
      (node (ref "U$2") (pin "5") (pinfunction "THERM_5") (pintype "bidirectional"))
    )
    (net (code "37") (name "Net-(U$2-VPCC)") (class "Default")
      (node (ref "R14") (pin "1") (pinfunction "1_1") (pintype "passive"))
      (node (ref "R15") (pin "2") (pinfunction "2_2") (pintype "passive"))
      (node (ref "U$2") (pin "2") (pinfunction "VPCC_2") (pintype "input"))
    )
    (net (code "38") (name "Net-(U$2-{slash}PG)") (class "Default")
      (node (ref "PWR") (pin "A") (pinfunction "A_A") (pintype "passive"))
      (node (ref "U$2") (pin "6") (pinfunction "/PG_6") (pintype "open_collector"))
    )
    (net (code "39") (name "Net-(U1-L1)") (class "Default")
      (node (ref "L2") (pin "1") (pinfunction "1_1") (pintype "passive"))
      (node (ref "U1") (pin "4") (pinfunction "L1_4") (pintype "passive"))
    )
    (net (code "40") (name "Net-(U1-L2)") (class "Default")
      (node (ref "L2") (pin "2") (pinfunction "2_2") (pintype "passive"))
      (node (ref "U1") (pin "2") (pinfunction "L2_2") (pintype "passive"))
    )
    (net (code "41") (name "OUT") (class "Default")
      (node (ref "C12") (pin "1") (pinfunction "1_1") (pintype "passive"))
      (node (ref "JP2") (pin "2") (pinfunction "2_2") (pintype "passive"))
      (node (ref "U1") (pin "5") (pinfunction "VIN_5") (pintype "power_in"))
      (node (ref "U1") (pin "6") (pinfunction "EN_6") (pintype "input"))
      (node (ref "U1") (pin "7") (pinfunction "PS/SYNC_7") (pintype "input"))
      (node (ref "U1") (pin "8") (pinfunction "VINA_8") (pintype "power_in"))
    )
    (net (code "42") (name "OUT_JUMP") (class "Default")
      (node (ref "JP2") (pin "1") (pinfunction "1_1") (pintype "passive"))
      (node (ref "U$2") (pin "1") (pinfunction "OUT_1") (pintype "power_in"))
      (node (ref "U$2") (pin "20") (pinfunction "OUT2_20") (pintype "power_in"))
    )
    (net (code "43") (name "RX") (class "Default")
      (node (ref "CC3200MOD") (pin "P46") (pinfunction "46_GPIO1_P46") (pintype "bidirectional"))
      (node (ref "FLASH") (pin "4") (pinfunction "4_4") (pintype "passive"))
      (node (ref "U11") (pin "GPIO_01") (pinfunction "GPIO_01_GPIO_01") (pintype "bidirectional"))
    )
    (net (code "44") (name "SOP2") (class "Default")
      (node (ref "CC3200MOD") (pin "P23") (pinfunction "23_SOP2_P23") (pintype "bidirectional"))
      (node (ref "FLASH") (pin "3") (pinfunction "3_3") (pintype "passive"))
      (node (ref "R3") (pin "1") (pinfunction "1_1") (pintype "passive"))
      (node (ref "SOP2") (pin "1") (pinfunction "1_1") (pintype "passive"))
      (node (ref "U11") (pin "GPIO_25") (pinfunction "GPIO_25_GPIO_25") (pintype "bidirectional"))
    )
    (net (code "45") (name "TX") (class "Default")
      (node (ref "CC3200MOD") (pin "P47") (pinfunction "47_GPO2_P47") (pintype "bidirectional"))
      (node (ref "FLASH") (pin "5") (pinfunction "5_5") (pintype "passive"))
      (node (ref "U11") (pin "GPIO_02") (pinfunction "GPIO_02_GPIO_02") (pintype "bidirectional"))
    )
    (net (code "46") (name "VCC") (class "Default")
      (node (ref "C3") (pin "1") (pinfunction "1_1") (pintype "passive"))
      (node (ref "C4") (pin "1") (pinfunction "1_1") (pintype "passive"))
      (node (ref "C8") (pin "1") (pinfunction "1_1") (pintype "passive"))
      (node (ref "CC3200MOD") (pin "P36") (pinfunction "36_VBAT_DCDC_ANA_P36") (pintype "bidirectional"))
      (node (ref "CC3200MOD") (pin "P37") (pinfunction "37_VBAT_DCDC_PA_P37") (pintype "bidirectional"))
      (node (ref "CC3200MOD") (pin "P40") (pinfunction "40_VBAT_DCDC_DIG_IO_P40") (pintype "bidirectional"))
      (node (ref "FLASH") (pin "2") (pinfunction "2_2") (pintype "passive"))
      (node (ref "R1") (pin "2") (pinfunction "2_2") (pintype "passive"))
      (node (ref "R2") (pin "2") (pinfunction "2_2") (pintype "passive"))
      (node (ref "SOP2") (pin "2") (pinfunction "2_2") (pintype "passive"))
      (node (ref "U$1") (pin "P3") (pinfunction "VDDIO_P3") (pintype "bidirectional"))
      (node (ref "U$1") (pin "P4") (pinfunction "VDDD_P4") (pintype "bidirectional"))
      (node (ref "U$1") (pin "P7") (pinfunction "VDDA_P7") (pintype "bidirectional"))
      (node (ref "U1") (pin "1") (pinfunction "VOUT_1") (pintype "output"))
      (node (ref "U1") (pin "10") (pinfunction "FB_10") (pintype "input"))
      (node (ref "U11") (pin "3.3V") (pinfunction "3.3V_3.3V") (pintype "bidirectional"))
    )
    (net (code "47") (name "unconnected-(CC3200MOD-13_NC-PadP13)") (class "Default")
      (node (ref "CC3200MOD") (pin "P13") (pinfunction "13_NC_P13") (pintype "bidirectional"))
    )
    (net (code "48") (name "unconnected-(CC3200MOD-14_NC-PadP14)") (class "Default")
      (node (ref "CC3200MOD") (pin "P14") (pinfunction "14_NC_P14") (pintype "bidirectional"))
    )
    (net (code "49") (name "unconnected-(CC3200MOD-15_NC-PadP15)") (class "Default")
      (node (ref "CC3200MOD") (pin "P15") (pinfunction "15_NC_P15") (pintype "bidirectional"))
    )
    (net (code "50") (name "unconnected-(CC3200MOD-17_NC-PadP17)") (class "Default")
      (node (ref "CC3200MOD") (pin "P17") (pinfunction "17_NC_P17") (pintype "bidirectional"))
    )
    (net (code "51") (name "unconnected-(CC3200MOD-20_NC-PadP20)") (class "Default")
      (node (ref "CC3200MOD") (pin "P20") (pinfunction "20_NC_P20") (pintype "bidirectional"))
    )
    (net (code "52") (name "unconnected-(CC3200MOD-21_JTAG_TCK-PadP21)") (class "Default")
      (node (ref "CC3200MOD") (pin "P21") (pinfunction "21_JTAG_TCK_P21") (pintype "bidirectional"))
    )
    (net (code "53") (name "unconnected-(CC3200MOD-22_JTAP_TMS-PadP22)") (class "Default")
      (node (ref "CC3200MOD") (pin "P22") (pinfunction "22_JTAP_TMS_P22") (pintype "bidirectional"))
    )
    (net (code "54") (name "unconnected-(CC3200MOD-24_SOP1-PadP24)") (class "Default")
      (node (ref "CC3200MOD") (pin "P24") (pinfunction "24_SOP1_P24") (pintype "bidirectional"))
    )
    (net (code "55") (name "unconnected-(CC3200MOD-25_ANTSEL1-PadP25)") (class "Default")
      (node (ref "CC3200MOD") (pin "P25") (pinfunction "25_ANTSEL1_P25") (pintype "bidirectional"))
    )
    (net (code "56") (name "unconnected-(CC3200MOD-26_ANTSEL2-PadP26)") (class "Default")
      (node (ref "CC3200MOD") (pin "P26") (pinfunction "26_ANTSEL2_P26") (pintype "bidirectional"))
    )
    (net (code "57") (name "unconnected-(CC3200MOD-29_NC-PadP29)") (class "Default")
      (node (ref "CC3200MOD") (pin "P29") (pinfunction "29_NC_P29") (pintype "bidirectional"))
    )
    (net (code "58") (name "unconnected-(CC3200MOD-33_NC-PadP33)") (class "Default")
      (node (ref "CC3200MOD") (pin "P33") (pinfunction "33_NC_P33") (pintype "bidirectional"))
    )
    (net (code "59") (name "unconnected-(CC3200MOD-34_SOP0-PadP34)") (class "Default")
      (node (ref "CC3200MOD") (pin "P34") (pinfunction "34_SOP0_P34") (pintype "bidirectional"))
    )
    (net (code "60") (name "unconnected-(CC3200MOD-39_VDD_ANA2-PadP39)") (class "Default")
      (node (ref "CC3200MOD") (pin "P39") (pinfunction "39_VDD_ANA2_P39") (pintype "bidirectional"))
    )
    (net (code "61") (name "unconnected-(CC3200MOD-41_NC-PadP41)") (class "Default")
      (node (ref "CC3200MOD") (pin "P41") (pinfunction "41_NC_P41") (pintype "bidirectional"))
    )
    (net (code "62") (name "unconnected-(CC3200MOD-44_GPIO0-PadP44)") (class "Default")
      (node (ref "CC3200MOD") (pin "P44") (pinfunction "44_GPIO0_P44") (pintype "bidirectional"))
    )
    (net (code "63") (name "unconnected-(CC3200MOD-45_NC-PadP45)") (class "Default")
      (node (ref "CC3200MOD") (pin "P45") (pinfunction "45_NC_P45") (pintype "bidirectional"))
    )
    (net (code "64") (name "unconnected-(J1-PAD1-PadNC1)") (class "Default")
      (node (ref "J1") (pin "NC1") (pinfunction "PAD1_NC1") (pintype "bidirectional"))
    )
    (net (code "65") (name "unconnected-(J1-PAD2-PadNC2)") (class "Default")
      (node (ref "J1") (pin "NC2") (pinfunction "PAD2_NC2") (pintype "bidirectional"))
    )
    (net (code "66") (name "unconnected-(U$1-CAP0-PadP6)") (class "Default")
      (node (ref "U$1") (pin "P6") (pinfunction "CAP0_P6") (pintype "bidirectional"))
    )
    (net (code "67") (name "unconnected-(U$1-CSB-PadP10)") (class "Default")
      (node (ref "U$1") (pin "P10") (pinfunction "CSB_P10") (pintype "bidirectional"))
    )
    (net (code "68") (name "unconnected-(U$1-PS-PadP11)") (class "Default")
      (node (ref "U$1") (pin "P11") (pinfunction "PS_P11") (pintype "bidirectional"))
    )
    (net (code "69") (name "unconnected-(U11-GPIO_09_NC-PadGPIO_09_GPIO_00_NC)") (class "Default")
      (node (ref "U11") (pin "GPIO_09_GPIO_00_NC") (pinfunction "GPIO_09_NC_GPIO_09_GPIO_00_NC") (pintype "bidirectional"))
    )
    (net (code "70") (name "unconnected-(U11-GPIO_25_NC-PadGPIO_25_GPIO_07_NC)") (class "Default")
      (node (ref "U11") (pin "GPIO_25_GPIO_07_NC") (pinfunction "GPIO_25_NC_GPIO_25_GPIO_07_NC") (pintype "bidirectional"))
    )
    (net (code "71") (name "unconnected-(U11-Pad5V)") (class "Default")
      (node (ref "U11") (pin "5V") (pinfunction "5V_5V") (pintype "bidirectional"))
    )
    (net (code "72") (name "unconnected-(U11-PadGPIO_00)") (class "Default")
      (node (ref "U11") (pin "GPIO_00") (pinfunction "GPIO_00_GPIO_00") (pintype "bidirectional"))
    )
    (net (code "73") (name "unconnected-(U11-PadGPIO_03_NC)") (class "Default")
      (node (ref "U11") (pin "GPIO_03_NC") (pinfunction "GPIO_03_NC_GPIO_03_NC") (pintype "bidirectional"))
    )
    (net (code "74") (name "unconnected-(U11-PadGPIO_04_NC)") (class "Default")
      (node (ref "U11") (pin "GPIO_04_NC") (pinfunction "GPIO_04_NC_GPIO_04_NC") (pintype "bidirectional"))
    )
    (net (code "75") (name "unconnected-(U11-PadGPIO_05_NC)") (class "Default")
      (node (ref "U11") (pin "GPIO_05_NC") (pinfunction "GPIO_05_NC_GPIO_05_NC") (pintype "bidirectional"))
    )
    (net (code "76") (name "unconnected-(U11-PadGPIO_07_NC)") (class "Default")
      (node (ref "U11") (pin "GPIO_07_NC") (pinfunction "GPIO_07_NC_GPIO_07_NC") (pintype "bidirectional"))
    )
    (net (code "77") (name "unconnected-(U11-PadGPIO_10_NC)") (class "Default")
      (node (ref "U11") (pin "GPIO_10_NC") (pinfunction "GPIO_10_NC_GPIO_10_NC") (pintype "bidirectional"))
    )
    (net (code "78") (name "unconnected-(U11-PadGPIO_11_NC)") (class "Default")
      (node (ref "U11") (pin "GPIO_11_NC") (pinfunction "GPIO_11_NC_GPIO_11_NC") (pintype "bidirectional"))
    )
    (net (code "79") (name "unconnected-(U11-PadGPIO_24_NC)") (class "Default")
      (node (ref "U11") (pin "GPIO_24_NC") (pinfunction "GPIO_24_NC_GPIO_24_NC") (pintype "bidirectional"))
    )
    (net (code "80") (name "unconnected-(U11-PadGPIO_28_NC)") (class "Default")
      (node (ref "U11") (pin "GPIO_28_NC") (pinfunction "GPIO_28_NC_GPIO_28_NC") (pintype "bidirectional"))
    )
    (net (code "81") (name "unconnected-(U11-PadGPIO_31)") (class "Default")
      (node (ref "U11") (pin "GPIO_31") (pinfunction "GPIO_31_GPIO_31") (pintype "bidirectional"))
    )
    (net (code "82") (name "unconnected-(U11-PadRESET_OUT)") (class "Default")
      (node (ref "U11") (pin "RESET_OUT") (pinfunction "RESET_OUT_RESET_OUT") (pintype "bidirectional"))
    )
    (net (code "83") (name "unconnected-(USB-Pad2)") (class "Default")
      (node (ref "USB") (pin "2") (pinfunction "2_2") (pintype "input"))
    )
    (net (code "84") (name "unconnected-(USB-Pad3)") (class "Default")
      (node (ref "USB") (pin "3") (pinfunction "3_3") (pintype "input"))
    )
    (net (code "85") (name "unconnected-(USB-Pad4)") (class "Default")
      (node (ref "USB") (pin "4") (pinfunction "4_4") (pintype "input"))
    )
  )
)
